# shift_register_paralel.net
KiCad netlist of a schematic drawn in EAGLE
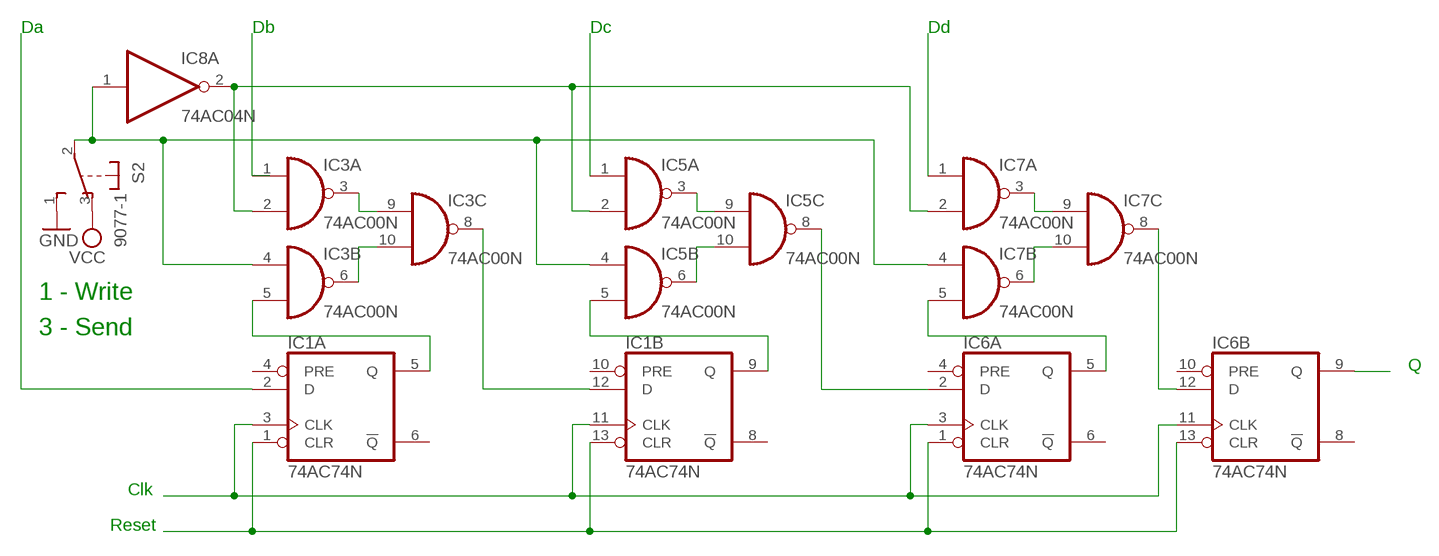
[diagram p0: schematic, sheet 1]

(export (version "E")
  (design (tool "Eeschema 10.0.6"))
  (components
    (comp (ref "IC1")
      (value "74AC74N")
      (footprint "eagle-import:DIL14")
      (libsource (lib "eagle-import") (part "7474NAC"))
    )
    (comp (ref "IC3")
      (value "74AC00N")
      (footprint "eagle-import:DIL14")
      (libsource (lib "eagle-import") (part "7400NAC"))
    )
    (comp (ref "IC5")
      (value "74AC00N")
      (footprint "eagle-import:DIL14")
      (libsource (lib "eagle-import") (part "7400NAC"))
    )
    (comp (ref "IC6")
      (value "74AC74N")
      (footprint "eagle-import:DIL14")
      (libsource (lib "eagle-import") (part "7474NAC"))
    )
    (comp (ref "IC7")
      (value "74AC00N")
      (footprint "eagle-import:DIL14")
      (libsource (lib "eagle-import") (part "7400NAC"))
    )
    (comp (ref "IC8")
      (value "74AC04N")
      (footprint "eagle-import:DIL14")
      (libsource (lib "eagle-import") (part "7404NAC"))
    )
    (comp (ref "S2")
      (value "9077-1")
      (footprint "eagle-import:9077-1")
      (libsource (lib "eagle-import") (part "9077-1"))
    )
  )
  (nets
    (net (code "1") (name "GND") (class "Default")
      (node (ref "S2") (pin "1") (pinfunction "S_1") (pintype "passive"))
    )
    (net (code "2") (name "Net-(IC1A-CLK)") (class "Default")
      (node (ref "IC1") (pin "11") (pinfunction "CLK_11") (pintype "input"))
      (node (ref "IC1") (pin "3") (pinfunction "CLK_3") (pintype "input"))
      (node (ref "IC6") (pin "11") (pinfunction "CLK_11") (pintype "input"))
      (node (ref "IC6") (pin "3") (pinfunction "CLK_3") (pintype "input"))
    )
    (net (code "3") (name "Net-(IC1A-CLR)") (class "Default")
      (node (ref "IC1") (pin "1") (pinfunction "CLR_1") (pintype "input"))
      (node (ref "IC1") (pin "13") (pinfunction "CLR_13") (pintype "input"))
      (node (ref "IC6") (pin "1") (pinfunction "CLR_1") (pintype "input"))
      (node (ref "IC6") (pin "13") (pinfunction "CLR_13") (pintype "input"))
    )
    (net (code "4") (name "Net-(IC1A-Q)") (class "Default")
      (node (ref "IC1") (pin "5") (pinfunction "Q_5") (pintype "output"))
      (node (ref "IC3") (pin "5") (pinfunction "I1_5") (pintype "input"))
    )
    (net (code "5") (name "Net-(IC1B-D)") (class "Default")
      (node (ref "IC1") (pin "12") (pinfunction "D_12") (pintype "input"))
      (node (ref "IC3") (pin "8") (pinfunction "O_8") (pintype "output"))
    )
    (net (code "6") (name "Net-(IC1B-Q)") (class "Default")
      (node (ref "IC1") (pin "9") (pinfunction "Q_9") (pintype "output"))
      (node (ref "IC5") (pin "5") (pinfunction "I1_5") (pintype "input"))
    )
    (net (code "7") (name "Net-(IC3A-I1)") (class "Default")
      (node (ref "IC3") (pin "2") (pinfunction "I1_2") (pintype "input"))
      (node (ref "IC5") (pin "2") (pinfunction "I1_2") (pintype "input"))
      (node (ref "IC7") (pin "2") (pinfunction "I1_2") (pintype "input"))
      (node (ref "IC8") (pin "2") (pinfunction "O_2") (pintype "output"))
    )
    (net (code "8") (name "Net-(IC3A-O)") (class "Default")
      (node (ref "IC3") (pin "3") (pinfunction "O_3") (pintype "output"))
      (node (ref "IC3") (pin "9") (pinfunction "I0_9") (pintype "input"))
    )
    (net (code "9") (name "Net-(IC3B-I0)") (class "Default")
      (node (ref "IC3") (pin "4") (pinfunction "I0_4") (pintype "input"))
      (node (ref "IC5") (pin "4") (pinfunction "I0_4") (pintype "input"))
      (node (ref "IC7") (pin "4") (pinfunction "I0_4") (pintype "input"))
      (node (ref "IC8") (pin "1") (pinfunction "I_1") (pintype "input"))
      (node (ref "S2") (pin "2") (pinfunction "P_2") (pintype "passive"))
    )
    (net (code "10") (name "Net-(IC3B-O)") (class "Default")
      (node (ref "IC3") (pin "10") (pinfunction "I1_10") (pintype "input"))
      (node (ref "IC3") (pin "6") (pinfunction "O_6") (pintype "output"))
    )
    (net (code "11") (name "Net-(IC5A-O)") (class "Default")
      (node (ref "IC5") (pin "3") (pinfunction "O_3") (pintype "output"))
      (node (ref "IC5") (pin "9") (pinfunction "I0_9") (pintype "input"))
    )
    (net (code "12") (name "Net-(IC5B-O)") (class "Default")
      (node (ref "IC5") (pin "10") (pinfunction "I1_10") (pintype "input"))
      (node (ref "IC5") (pin "6") (pinfunction "O_6") (pintype "output"))
    )
    (net (code "13") (name "Net-(IC5C-O)") (class "Default")
      (node (ref "IC5") (pin "8") (pinfunction "O_8") (pintype "output"))
      (node (ref "IC6") (pin "2") (pinfunction "D_2") (pintype "input"))
    )
    (net (code "14") (name "Net-(IC6A-Q)") (class "Default")
      (node (ref "IC6") (pin "5") (pinfunction "Q_5") (pintype "output"))
      (node (ref "IC7") (pin "5") (pinfunction "I1_5") (pintype "input"))
    )
    (net (code "15") (name "Net-(IC6B-D)") (class "Default")
      (node (ref "IC6") (pin "12") (pinfunction "D_12") (pintype "input"))
      (node (ref "IC7") (pin "8") (pinfunction "O_8") (pintype "output"))
    )
    (net (code "16") (name "Net-(IC7A-O)") (class "Default")
      (node (ref "IC7") (pin "3") (pinfunction "O_3") (pintype "output"))
      (node (ref "IC7") (pin "9") (pinfunction "I0_9") (pintype "input"))
    )
    (net (code "17") (name "Net-(IC7B-O)") (class "Default")
      (node (ref "IC7") (pin "10") (pinfunction "I1_10") (pintype "input"))
      (node (ref "IC7") (pin "6") (pinfunction "O_6") (pintype "output"))
    )
    (net (code "18") (name "VCC") (class "Default")
      (node (ref "S2") (pin "3") (pinfunction "O_3") (pintype "passive"))
    )
    (net (code "19") (name "unconnected-(IC1A-D-Pad2)") (class "Default")
      (node (ref "IC1") (pin "2") (pinfunction "D_2") (pintype "input"))
    )
    (net (code "20") (name "unconnected-(IC1A-PRE-Pad4)") (class "Default")
      (node (ref "IC1") (pin "4") (pinfunction "PRE_4") (pintype "input"))
    )
    (net (code "21") (name "unconnected-(IC1A-~{Q}-Pad6)") (class "Default")
      (node (ref "IC1") (pin "6") (pinfunction "~{Q}_6") (pintype "output"))
    )
    (net (code "22") (name "unconnected-(IC1B-PRE-Pad10)") (class "Default")
      (node (ref "IC1") (pin "10") (pinfunction "PRE_10") (pintype "input"))
    )
    (net (code "23") (name "unconnected-(IC1B-~{Q}-Pad8)") (class "Default")
      (node (ref "IC1") (pin "8") (pinfunction "~{Q}_8") (pintype "output"))
    )
    (net (code "24") (name "unconnected-(IC3A-I0-Pad1)") (class "Default")
      (node (ref "IC3") (pin "1") (pinfunction "I0_1") (pintype "input"))
    )
    (net (code "25") (name "unconnected-(IC5A-I0-Pad1)") (class "Default")
      (node (ref "IC5") (pin "1") (pinfunction "I0_1") (pintype "input"))
    )
    (net (code "26") (name "unconnected-(IC6A-PRE-Pad4)") (class "Default")
      (node (ref "IC6") (pin "4") (pinfunction "PRE_4") (pintype "input"))
    )
    (net (code "27") (name "unconnected-(IC6A-~{Q}-Pad6)") (class "Default")
      (node (ref "IC6") (pin "6") (pinfunction "~{Q}_6") (pintype "output"))
    )
    (net (code "28") (name "unconnected-(IC6B-PRE-Pad10)") (class "Default")
      (node (ref "IC6") (pin "10") (pinfunction "PRE_10") (pintype "input"))
    )
    (net (code "29") (name "unconnected-(IC6B-Q-Pad9)") (class "Default")
      (node (ref "IC6") (pin "9") (pinfunction "Q_9") (pintype "output"))
    )
    (net (code "30") (name "unconnected-(IC6B-~{Q}-Pad8)") (class "Default")
      (node (ref "IC6") (pin "8") (pinfunction "~{Q}_8") (pintype "output"))
    )
    (net (code "31") (name "unconnected-(IC7A-I0-Pad1)") (class "Default")
      (node (ref "IC7") (pin "1") (pinfunction "I0_1") (pintype "input"))
    )
  )
)
